# piezo-buffer-and-preamp-ritter_V0-2-thru.net
KiCad netlist of a schematic drawn in EAGLE
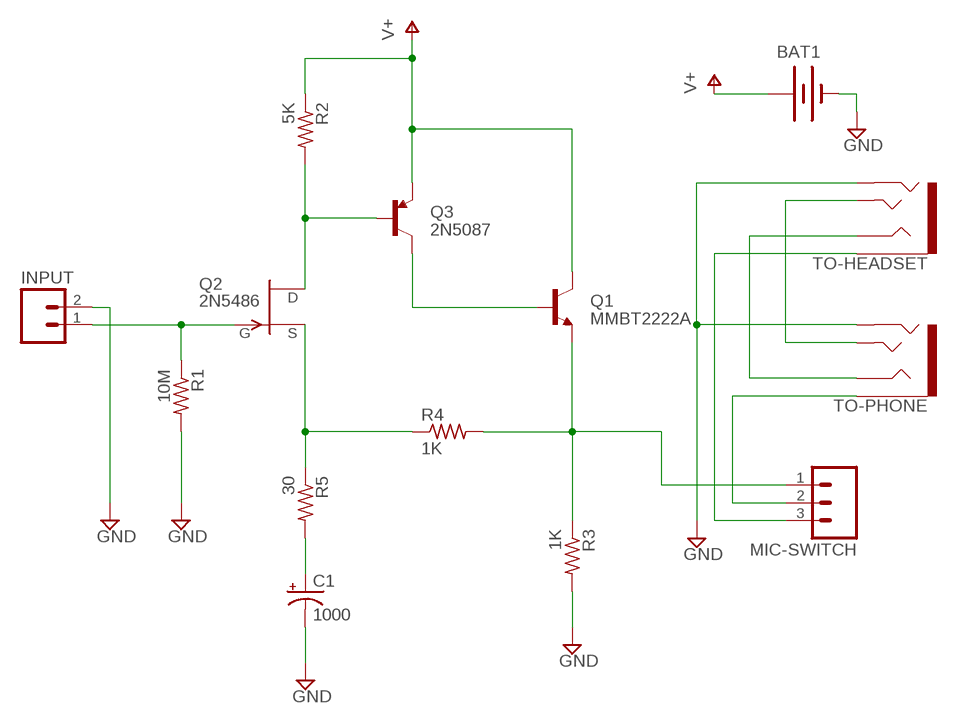
[diagram p0: schematic, sheet 1]

(export (version "E")
  (design (tool "Eeschema 10.0.6"))
  (components
    (comp (ref "BAT1")
      (value "BATTERYAAA-KIT")
      (footprint "eagle-import:BATTERY-AAA-KIT")
      (libsource (lib "eagle-import") (part "BATTERYAAA-KIT"))
    )
    (comp (ref "C1")
      (value "1000")
      (footprint "eagle-import:CPOL-RADIAL-1000UF-25V")
      (libsource (lib "eagle-import") (part "CAP_POLPTH4"))
    )
    (comp (ref "INPUT")
      (value "M02LOCK")
      (footprint "eagle-import:1X02_LOCK")
      (libsource (lib "eagle-import") (part "M02LOCK"))
    )
    (comp (ref "MIC-SWITCH")
      (value "M03LOCK")
      (footprint "eagle-import:1X03_LOCK")
      (libsource (lib "eagle-import") (part "M03LOCK"))
    )
    (comp (ref "Q1")
      (value "MMBT2222A")
      (footprint "eagle-import:TO-92")
      (libsource (lib "eagle-import") (part "TRANSISTOR_NPNTO92"))
    )
    (comp (ref "Q2")
      (value "2N5486")
      (footprint "eagle-import:TO92-")
      (libsource (lib "eagle-import") (part "?5482N6"))
    )
    (comp (ref "Q3")
      (value "2N5087")
      (footprint "eagle-import:TO-92")
      (libsource (lib "eagle-import") (part "TRANSISTOR_PNPTO92"))
    )
    (comp (ref "R1")
      (value "10M")
      (footprint "eagle-import:V526-0")
      (libsource (lib "eagle-import") (part "R-US_V526-0"))
    )
    (comp (ref "R2")
      (value "5K")
      (footprint "eagle-import:V526-0")
      (libsource (lib "eagle-import") (part "R-US_V526-0"))
    )
    (comp (ref "R3")
      (value "1K")
      (footprint "eagle-import:V526-0")
      (libsource (lib "eagle-import") (part "R-US_V526-0"))
    )
    (comp (ref "R4")
      (value "1K")
      (footprint "eagle-import:V526-0")
      (libsource (lib "eagle-import") (part "R-US_V526-0"))
    )
    (comp (ref "R5")
      (value "30")
      (footprint "eagle-import:V526-0")
      (libsource (lib "eagle-import") (part "R-US_V526-0"))
    )
    (comp (ref "TO-HEADSET")
      (value "AUDIO-JACK3")
      (footprint "eagle-import:AUDIO-JACK-TRRS-SMD")
      (libsource (lib "eagle-import") (part "AUDIO-JACK3"))
    )
    (comp (ref "TO-PHONE")
      (value "AUDIO-JACK3")
      (footprint "eagle-import:AUDIO-JACK-TRRS-SMD")
      (libsource (lib "eagle-import") (part "AUDIO-JACK3"))
    )
  )
  (nets
    (net (code "1") (name "GND") (class "Default")
      (node (ref "BAT1") (pin "GND@1") (pinfunction "-_GND@1") (pintype "power_in"))
      (node (ref "C1") (pin "-") (pinfunction "-_-") (pintype "passive"))
      (node (ref "INPUT") (pin "2") (pinfunction "2_2") (pintype "passive"))
      (node (ref "R1") (pin "2") (pinfunction "2_2") (pintype "passive"))
      (node (ref "R3") (pin "2") (pinfunction "2_2") (pintype "passive"))
      (node (ref "TO-HEADSET") (pin "RING2") (pinfunction "RING2_RING2") (pintype "bidirectional"))
      (node (ref "TO-PHONE") (pin "RING2") (pinfunction "RING2_RING2") (pintype "bidirectional"))
    )
    (net (code "2") (name "Net-(C1-Pad+)") (class "Default")
      (node (ref "C1") (pin "+") (pinfunction "+_+") (pintype "passive"))
      (node (ref "R5") (pin "2") (pinfunction "2_2") (pintype "passive"))
    )
    (net (code "3") (name "Net-(MIC-SWITCH-Pad2)") (class "Default")
      (node (ref "MIC-SWITCH") (pin "2") (pinfunction "2_2") (pintype "passive"))
      (node (ref "TO-PHONE") (pin "EARTH") (pinfunction "EARTH_EARTH") (pintype "bidirectional"))
    )
    (net (code "4") (name "Net-(MIC-SWITCH-Pad3)") (class "Default")
      (node (ref "MIC-SWITCH") (pin "3") (pinfunction "3_3") (pintype "passive"))
      (node (ref "TO-HEADSET") (pin "EARTH") (pinfunction "EARTH_EARTH") (pintype "bidirectional"))
    )
    (net (code "5") (name "Net-(Q1-B)") (class "Default")
      (node (ref "Q1") (pin "2") (pinfunction "B_2") (pintype "passive"))
      (node (ref "Q3") (pin "3") (pinfunction "C_3") (pintype "passive"))
    )
    (net (code "6") (name "Net-(Q1-E)") (class "Default")
      (node (ref "MIC-SWITCH") (pin "1") (pinfunction "1_1") (pintype "passive"))
      (node (ref "Q1") (pin "1") (pinfunction "E_1") (pintype "passive"))
      (node (ref "R3") (pin "1") (pinfunction "1_1") (pintype "passive"))
      (node (ref "R4") (pin "2") (pinfunction "2_2") (pintype "passive"))
    )
    (net (code "7") (name "Net-(Q2-D)") (class "Default")
      (node (ref "Q2") (pin "3") (pinfunction "D_3") (pintype "passive"))
      (node (ref "Q3") (pin "2") (pinfunction "B_2") (pintype "passive"))
      (node (ref "R2") (pin "2") (pinfunction "2_2") (pintype "passive"))
    )
    (net (code "8") (name "Net-(Q2-G)") (class "Default")
      (node (ref "INPUT") (pin "1") (pinfunction "1_1") (pintype "passive"))
      (node (ref "Q2") (pin "1") (pinfunction "G_1") (pintype "passive"))
      (node (ref "R1") (pin "1") (pinfunction "1_1") (pintype "passive"))
    )
    (net (code "9") (name "Net-(Q2-S)") (class "Default")
      (node (ref "Q2") (pin "2") (pinfunction "S_2") (pintype "passive"))
      (node (ref "R4") (pin "1") (pinfunction "1_1") (pintype "passive"))
      (node (ref "R5") (pin "1") (pinfunction "1_1") (pintype "passive"))
    )
    (net (code "10") (name "Net-(TO-HEADSET-PadRING1)") (class "Default")
      (node (ref "TO-HEADSET") (pin "RING1") (pinfunction "RING1_RING1") (pintype "bidirectional"))
      (node (ref "TO-PHONE") (pin "RING1") (pinfunction "RING1_RING1") (pintype "bidirectional"))
    )
    (net (code "11") (name "Net-(TO-HEADSET-PadTIP)") (class "Default")
      (node (ref "TO-HEADSET") (pin "TIP") (pinfunction "TIP_TIP") (pintype "bidirectional"))
      (node (ref "TO-PHONE") (pin "TIP") (pinfunction "TIP_TIP") (pintype "bidirectional"))
    )
    (net (code "12") (name "V+") (class "Default")
      (node (ref "BAT1") (pin "PWR@1") (pinfunction "+_PWR@1") (pintype "power_in"))
      (node (ref "Q1") (pin "3") (pinfunction "C_3") (pintype "passive"))
      (node (ref "Q3") (pin "1") (pinfunction "E_1") (pintype "passive"))
      (node (ref "R2") (pin "1") (pinfunction "1_1") (pintype "passive"))
    )
  )
)
